# Sheet2.net
KiCad netlist of a schematic drawn in Altium Designer
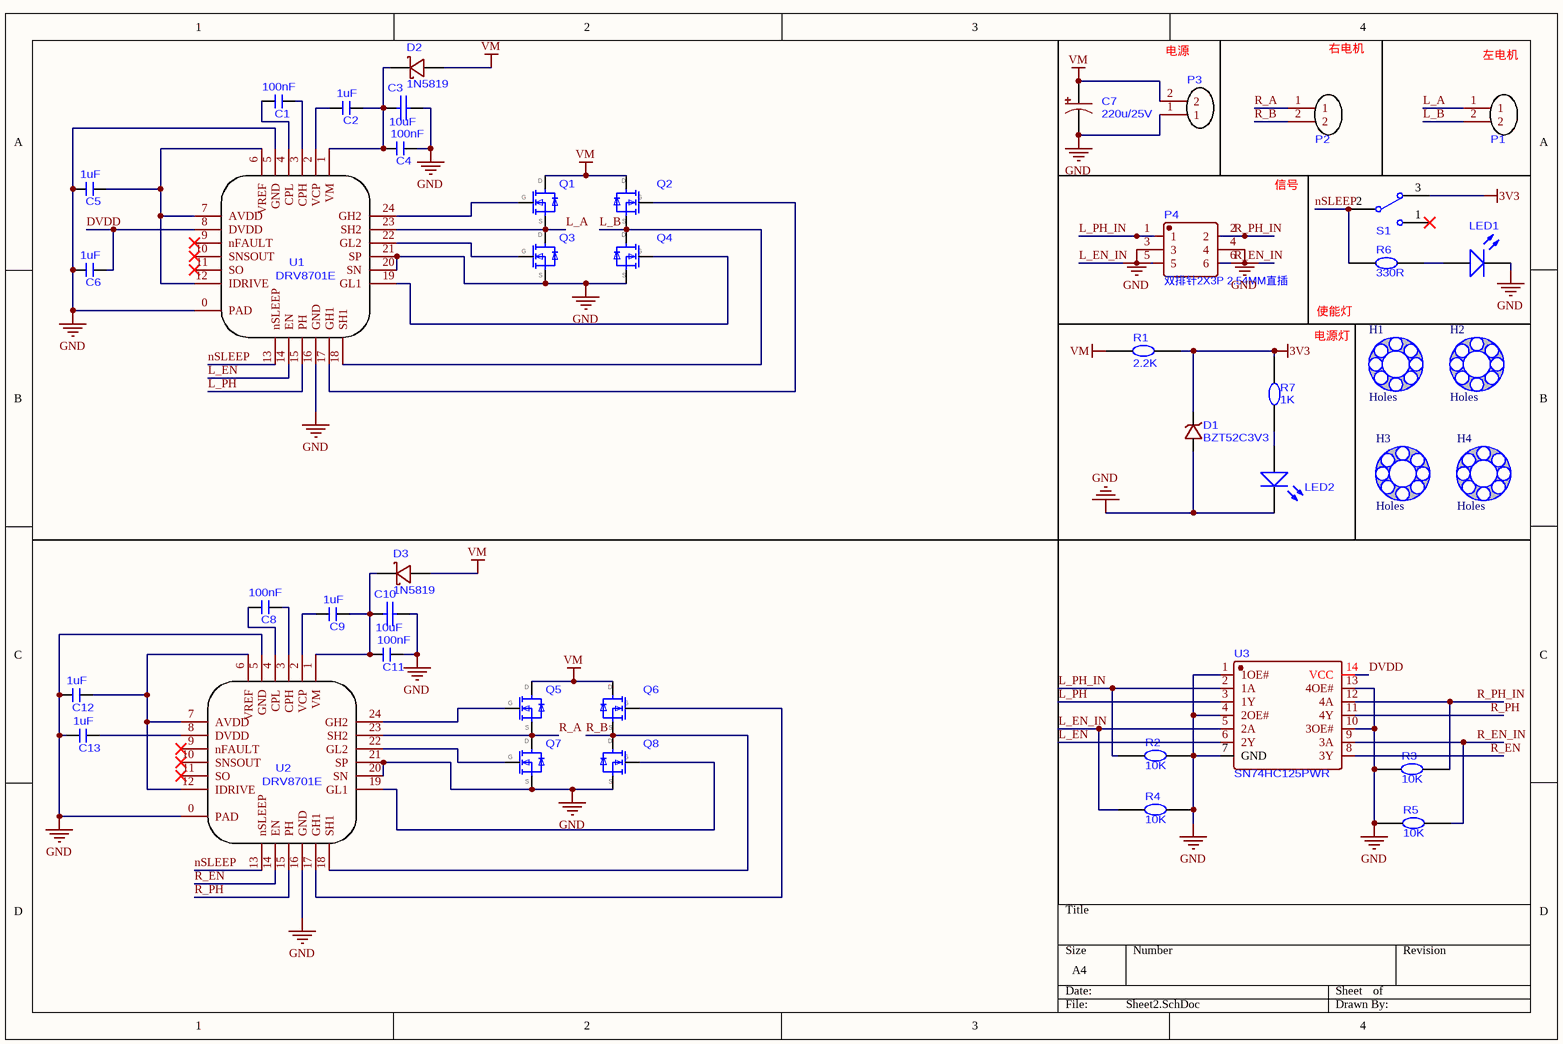
[diagram p0: Sheet2.SchDoc]

(export (version "E")
  (design (tool "Eeschema 10.0.6"))
  (components
    (comp (ref "C1") (value "100nF") (footprint "0603C") (libsource (lib "Schlib1") (part "0603-C")))
    (comp (ref "C2") (value "1uF") (footprint "0603C") (libsource (lib "Schlib1") (part "0603-C")))
    (comp (ref "C3") (value "10uF") (footprint "0805-C") (libsource (lib "Schlib1") (part "0805-C")))
    (comp (ref "C4") (value "100nF") (footprint "0603C") (libsource (lib "Schlib1") (part "0603-C")))
    (comp (ref "C5") (value "1uF") (footprint "0603C") (libsource (lib "Schlib1") (part "0603-C")))
    (comp (ref "C6") (value "1uF") (footprint "0603C") (libsource (lib "Schlib1") (part "0603-C")))
    (comp (ref "C7") (value "220u/25V") (footprint "220UF_25V") (libsource (lib "Schlib1") (part "220u/25V")))
    (comp (ref "C8") (value "100nF") (footprint "0603C") (libsource (lib "Schlib1") (part "0603-C")))
    (comp (ref "C9") (value "1uF") (footprint "0603C") (libsource (lib "Schlib1") (part "0603-C")))
    (comp (ref "C10") (value "10uF") (footprint "0805-C") (libsource (lib "Schlib1") (part "0805-C")))
    (comp (ref "C11") (value "100nF") (footprint "0603C") (libsource (lib "Schlib1") (part "0603-C")))
    (comp (ref "C12") (value "1uF") (footprint "0603C") (libsource (lib "Schlib1") (part "0603-C")))
    (comp (ref "C13") (value "1uF") (footprint "0603C") (libsource (lib "Schlib1") (part "0603-C")))
    (comp (ref "D1") (value "BZT52C3V3") (footprint "SOD-123") (libsource (lib "Schlib1") (part "BZT52C3V3")))
    (comp (ref "D2") (value "1N5819") (footprint "1N5819") (libsource (lib "Schlib1") (part "1N5819")))
    (comp (ref "D3") (value "1N5819") (footprint "1N5819") (libsource (lib "Schlib1") (part "1N5819")))
    (comp (ref "H1")
      (value "Holes")
      (footprint "M3-星月孔")
      (description "holes in the corner of the bord")
      (libsource (lib "Schlib1") (part "星月孔"))
    )
    (comp (ref "H2")
      (value "Holes")
      (footprint "M3-星月孔")
      (description "holes in the corner of the bord")
      (libsource (lib "Schlib1") (part "星月孔"))
    )
    (comp (ref "H3")
      (value "Holes")
      (footprint "M3-星月孔")
      (description "holes in the corner of the bord")
      (libsource (lib "Schlib1") (part "星月孔"))
    )
    (comp (ref "H4")
      (value "Holes")
      (footprint "M3-星月孔")
      (description "holes in the corner of the bord")
      (libsource (lib "Schlib1") (part "星月孔"))
    )
    (comp (ref "LED1") (value "LED") (footprint "0603LED") (libsource (lib "Schlib1") (part "LED")))
    (comp (ref "LED2") (value "LED") (footprint "0603LED") (libsource (lib "Schlib1") (part "LED")))
    (comp (ref "P1") (value "5.08-2P") (footprint "2P-5.08MM") (libsource (lib "Schlib1") (part "5.08-2P")))
    (comp (ref "P2") (value "5.08-2P") (footprint "2P-5.08MM") (libsource (lib "Schlib1") (part "5.08-2P")))
    (comp (ref "P3") (value "5.08-2P") (footprint "2P-5.08MM") (libsource (lib "Schlib1") (part "5.08-2P")))
    (comp (ref "P4")
      (value "双排针2X3P 2.54MM直插")
      (footprint "2X3 2.54")
      (libsource (lib "Schlib1") (part "双排针2X3P 2.54MM直插"))
    )
    (comp (ref "Q1")
      (value "TPH1R403NL_L")
      (footprint "TPH1R403NL")
      (libsource (lib "Schlib1") (part "TPH1R403NL_L"))
    )
    (comp (ref "Q2")
      (value "TPH1R403NL_L")
      (footprint "TPH1R403NL")
      (libsource (lib "") (part "TPH1R403NL_L_1"))
    )
    (comp (ref "Q3")
      (value "TPH1R403NL_L")
      (footprint "TPH1R403NL")
      (libsource (lib "Schlib1") (part "TPH1R403NL_L"))
    )
    (comp (ref "Q4")
      (value "TPH1R403NL_L")
      (footprint "TPH1R403NL")
      (libsource (lib "") (part "TPH1R403NL_L_1"))
    )
    (comp (ref "Q5")
      (value "TPH1R403NL_L")
      (footprint "TPH1R403NL")
      (libsource (lib "Schlib1") (part "TPH1R403NL_L"))
    )
    (comp (ref "Q6")
      (value "TPH1R403NL_L")
      (footprint "TPH1R403NL")
      (libsource (lib "") (part "TPH1R403NL_L_1"))
    )
    (comp (ref "Q7")
      (value "TPH1R403NL_L")
      (footprint "TPH1R403NL")
      (libsource (lib "Schlib1") (part "TPH1R403NL_L"))
    )
    (comp (ref "Q8")
      (value "TPH1R403NL_L")
      (footprint "TPH1R403NL")
      (libsource (lib "") (part "TPH1R403NL_L_1"))
    )
    (comp (ref "R1") (value "2.2K") (footprint "0603R") (libsource (lib "Schlib1") (part "0603-R")))
    (comp (ref "R2") (value "10K") (footprint "0603R") (libsource (lib "Schlib1") (part "0603-R")))
    (comp (ref "R3") (value "10K") (footprint "0603R") (libsource (lib "Schlib1") (part "0603-R")))
    (comp (ref "R4") (value "10K") (footprint "0603R") (libsource (lib "Schlib1") (part "0603-R")))
    (comp (ref "R5") (value "10K") (footprint "0603R") (libsource (lib "Schlib1") (part "0603-R")))
    (comp (ref "R6") (value "330R") (footprint "0603R") (libsource (lib "Schlib1") (part "0603-R")))
    (comp (ref "R7") (value "1K") (footprint "0603R") (libsource (lib "Schlib1") (part "0603-R")))
    (comp (ref "S1")
      (value "SW1:T8013")
      (footprint "SW1_T8013")
      (libsource (lib "Schlib1") (part "SW1{colon}T8013"))
    )
    (comp (ref "U1") (value "DRV8701E") (footprint "DRV8701E") (libsource (lib "Schlib1") (part "DRV8701E")))
    (comp (ref "U2") (value "DRV8701E") (footprint "DRV8701E") (libsource (lib "Schlib1") (part "DRV8701E")))
    (comp (ref "U3")
      (value "SN74HC125PWR")
      (footprint "TSSOP-14_L5.0-W4.4-P0.65-LS6.5-BL")
      (libsource (lib "Schlib1") (part "SN74HC125PWR"))
    )
  )
  (nets
    (net (code "1") (name "/DVDD") (class "Default")
      (node (ref "C6") (pin "2") (pinfunction "2_2") (pintype "passive"))
      (node (ref "U1") (pin "8") (pinfunction "DVDD_8") (pintype "passive"))
      (node (ref "U3") (pin "14") (pinfunction "VCC_14") (pintype "passive"))
    )
    (net (code "2") (name "/L_A") (class "Default")
      (node (ref "P1") (pin "1") (pinfunction "1_1") (pintype "passive"))
      (node (ref "Q1") (pin "3") (pinfunction "S_3") (pintype "passive"))
      (node (ref "Q3") (pin "1") (pinfunction "D_1") (pintype "passive"))
      (node (ref "U1") (pin "23") (pinfunction "SH2_23") (pintype "passive"))
    )
    (net (code "3") (name "/L_B") (class "Default")
      (node (ref "P1") (pin "2") (pinfunction "2_2") (pintype "passive"))
      (node (ref "Q2") (pin "3") (pinfunction "S_3") (pintype "passive"))
      (node (ref "Q4") (pin "1") (pinfunction "D_1") (pintype "passive"))
      (node (ref "U1") (pin "18") (pinfunction "SH1_18") (pintype "passive"))
    )
    (net (code "4") (name "/L_EN") (class "Default")
      (node (ref "U1") (pin "14") (pinfunction "EN_14") (pintype "passive"))
      (node (ref "U3") (pin "6") (pinfunction "2Y_6") (pintype "passive"))
    )
    (net (code "5") (name "/L_EN_IN") (class "Default")
      (node (ref "P4") (pin "5") (pinfunction "5_5") (pintype "passive"))
      (node (ref "R4") (pin "1") (pinfunction "1_1") (pintype "passive"))
      (node (ref "U3") (pin "5") (pinfunction "2A_5") (pintype "passive"))
    )
    (net (code "6") (name "/L_PH") (class "Default")
      (node (ref "U1") (pin "15") (pinfunction "PH_15") (pintype "passive"))
      (node (ref "U3") (pin "3") (pinfunction "1Y_3") (pintype "passive"))
    )
    (net (code "7") (name "/L_PH_IN") (class "Default")
      (node (ref "P4") (pin "1") (pinfunction "1_1") (pintype "passive"))
      (node (ref "R2") (pin "1") (pinfunction "1_1") (pintype "passive"))
      (node (ref "U3") (pin "2") (pinfunction "1A_2") (pintype "passive"))
    )
    (net (code "8") (name "/R_A") (class "Default")
      (node (ref "P2") (pin "1") (pinfunction "1_1") (pintype "passive"))
      (node (ref "Q5") (pin "3") (pinfunction "S_3") (pintype "passive"))
      (node (ref "Q7") (pin "1") (pinfunction "D_1") (pintype "passive"))
      (node (ref "U2") (pin "23") (pinfunction "SH2_23") (pintype "passive"))
    )
    (net (code "9") (name "/R_B") (class "Default")
      (node (ref "P2") (pin "2") (pinfunction "2_2") (pintype "passive"))
      (node (ref "Q6") (pin "3") (pinfunction "S_3") (pintype "passive"))
      (node (ref "Q8") (pin "1") (pinfunction "D_1") (pintype "passive"))
      (node (ref "U2") (pin "18") (pinfunction "SH1_18") (pintype "passive"))
    )
    (net (code "10") (name "/R_EN") (class "Default")
      (node (ref "U2") (pin "14") (pinfunction "EN_14") (pintype "passive"))
      (node (ref "U3") (pin "8") (pinfunction "3Y_8") (pintype "passive"))
    )
    (net (code "11") (name "/R_EN_IN") (class "Default")
      (node (ref "P4") (pin "6") (pinfunction "6_6") (pintype "passive"))
      (node (ref "R5") (pin "2") (pinfunction "2_2") (pintype "passive"))
      (node (ref "U3") (pin "9") (pinfunction "3A_9") (pintype "passive"))
    )
    (net (code "12") (name "/R_PH") (class "Default")
      (node (ref "U2") (pin "15") (pinfunction "PH_15") (pintype "passive"))
      (node (ref "U3") (pin "11") (pinfunction "4Y_11") (pintype "passive"))
    )
    (net (code "13") (name "/R_PH_IN") (class "Default")
      (node (ref "P4") (pin "2") (pinfunction "2_2") (pintype "passive"))
      (node (ref "R3") (pin "2") (pinfunction "2_2") (pintype "passive"))
      (node (ref "U3") (pin "12") (pinfunction "4A_12") (pintype "passive"))
    )
    (net (code "14") (name "/nSLEEP") (class "Default")
      (node (ref "R6") (pin "1") (pinfunction "1_1") (pintype "passive"))
      (node (ref "S1") (pin "2") (pinfunction "2_2") (pintype "passive"))
      (node (ref "U1") (pin "13") (pinfunction "nSLEEP_13") (pintype "passive"))
      (node (ref "U2") (pin "13") (pinfunction "nSLEEP_13") (pintype "passive"))
    )
    (net (code "15") (name "3V3") (class "Default")
      (node (ref "D1") (pin "2") (pinfunction "K_2") (pintype "passive"))
      (node (ref "R1") (pin "2") (pinfunction "2_2") (pintype "passive"))
      (node (ref "R7") (pin "2") (pinfunction "2_2") (pintype "passive"))
      (node (ref "S1") (pin "3") (pinfunction "3_3") (pintype "passive"))
    )
    (net (code "16") (name "GND") (class "Default")
      (node (ref "C10") (pin "1") (pinfunction "1_1") (pintype "passive"))
      (node (ref "C11") (pin "1") (pinfunction "1_1") (pintype "passive"))
      (node (ref "C12") (pin "2") (pinfunction "2_2") (pintype "passive"))
      (node (ref "C13") (pin "1") (pinfunction "1_1") (pintype "passive"))
      (node (ref "C3") (pin "1") (pinfunction "1_1") (pintype "passive"))
      (node (ref "C4") (pin "1") (pinfunction "1_1") (pintype "passive"))
      (node (ref "C5") (pin "2") (pinfunction "2_2") (pintype "passive"))
      (node (ref "C6") (pin "1") (pinfunction "1_1") (pintype "passive"))
      (node (ref "C7") (pin "2") (pinfunction "2_2") (pintype "passive"))
      (node (ref "D1") (pin "1") (pinfunction "A_1") (pintype "passive"))
      (node (ref "LED1") (pin "2") (pinfunction "K_2") (pintype "passive"))
      (node (ref "LED2") (pin "2") (pinfunction "K_2") (pintype "passive"))
      (node (ref "P3") (pin "1") (pinfunction "1_1") (pintype "passive"))
      (node (ref "P4") (pin "3") (pinfunction "3_3") (pintype "passive"))
      (node (ref "P4") (pin "4") (pinfunction "4_4") (pintype "passive"))
      (node (ref "Q3") (pin "3") (pinfunction "S_3") (pintype "passive"))
      (node (ref "Q4") (pin "3") (pinfunction "S_3") (pintype "passive"))
      (node (ref "Q7") (pin "3") (pinfunction "S_3") (pintype "passive"))
      (node (ref "Q8") (pin "3") (pinfunction "S_3") (pintype "passive"))
      (node (ref "R2") (pin "2") (pinfunction "2_2") (pintype "passive"))
      (node (ref "R3") (pin "1") (pinfunction "1_1") (pintype "passive"))
      (node (ref "R4") (pin "2") (pinfunction "2_2") (pintype "passive"))
      (node (ref "R5") (pin "1") (pinfunction "1_1") (pintype "passive"))
      (node (ref "U1") (pin "0") (pinfunction "PAD_0") (pintype "passive"))
      (node (ref "U1") (pin "16") (pinfunction "GND_16") (pintype "passive"))
      (node (ref "U1") (pin "20") (pinfunction "SN_20") (pintype "passive"))
      (node (ref "U1") (pin "21") (pinfunction "SP_21") (pintype "passive"))
      (node (ref "U1") (pin "5") (pinfunction "GND_5") (pintype "passive"))
      (node (ref "U2") (pin "0") (pinfunction "PAD_0") (pintype "passive"))
      (node (ref "U2") (pin "16") (pinfunction "GND_16") (pintype "passive"))
      (node (ref "U2") (pin "20") (pinfunction "SN_20") (pintype "passive"))
      (node (ref "U2") (pin "21") (pinfunction "SP_21") (pintype "passive"))
      (node (ref "U2") (pin "5") (pinfunction "GND_5") (pintype "passive"))
      (node (ref "U3") (pin "1") (pinfunction "1OE#_1") (pintype "passive"))
      (node (ref "U3") (pin "10") (pinfunction "3OE#_10") (pintype "passive"))
      (node (ref "U3") (pin "13") (pinfunction "4OE#_13") (pintype "passive"))
      (node (ref "U3") (pin "4") (pinfunction "2OE#_4") (pintype "passive"))
      (node (ref "U3") (pin "7") (pinfunction "GND_7") (pintype "passive"))
    )
    (net (code "17") (name "Net-(LED1-Pad1)") (class "Default")
      (node (ref "LED1") (pin "1") (pinfunction "1_1") (pintype "passive"))
      (node (ref "R6") (pin "2") (pinfunction "2_2") (pintype "passive"))
    )
    (net (code "18") (name "Net-(LED2-Pad1)") (class "Default")
      (node (ref "LED2") (pin "1") (pinfunction "1_1") (pintype "passive"))
      (node (ref "R7") (pin "1") (pinfunction "1_1") (pintype "passive"))
    )
    (net (code "19") (name "Net-(Q1-G)") (class "Default")
      (node (ref "Q1") (pin "2") (pinfunction "G_2") (pintype "passive"))
      (node (ref "U1") (pin "24") (pinfunction "GH2_24") (pintype "passive"))
    )
    (net (code "20") (name "Net-(Q2-G)") (class "Default")
      (node (ref "Q2") (pin "2") (pinfunction "G_2") (pintype "passive"))
      (node (ref "U1") (pin "17") (pinfunction "GH1_17") (pintype "passive"))
    )
    (net (code "21") (name "Net-(Q3-G)") (class "Default")
      (node (ref "Q3") (pin "2") (pinfunction "G_2") (pintype "passive"))
      (node (ref "U1") (pin "22") (pinfunction "GL2_22") (pintype "passive"))
    )
    (net (code "22") (name "Net-(Q4-G)") (class "Default")
      (node (ref "Q4") (pin "2") (pinfunction "G_2") (pintype "passive"))
      (node (ref "U1") (pin "19") (pinfunction "GL1_19") (pintype "passive"))
    )
    (net (code "23") (name "Net-(Q5-G)") (class "Default")
      (node (ref "Q5") (pin "2") (pinfunction "G_2") (pintype "passive"))
      (node (ref "U2") (pin "24") (pinfunction "GH2_24") (pintype "passive"))
    )
    (net (code "24") (name "Net-(Q6-G)") (class "Default")
      (node (ref "Q6") (pin "2") (pinfunction "G_2") (pintype "passive"))
      (node (ref "U2") (pin "17") (pinfunction "GH1_17") (pintype "passive"))
    )
    (net (code "25") (name "Net-(Q7-G)") (class "Default")
      (node (ref "Q7") (pin "2") (pinfunction "G_2") (pintype "passive"))
      (node (ref "U2") (pin "22") (pinfunction "GL2_22") (pintype "passive"))
    )
    (net (code "26") (name "Net-(Q8-G)") (class "Default")
      (node (ref "Q8") (pin "2") (pinfunction "G_2") (pintype "passive"))
      (node (ref "U2") (pin "19") (pinfunction "GL1_19") (pintype "passive"))
    )
    (net (code "27") (name "Net-(U1-AVDD)") (class "Default")
      (node (ref "C5") (pin "1") (pinfunction "1_1") (pintype "passive"))
      (node (ref "U1") (pin "12") (pinfunction "IDRIVE_12") (pintype "passive"))
      (node (ref "U1") (pin "6") (pinfunction "VREF_6") (pintype "passive"))
      (node (ref "U1") (pin "7") (pinfunction "AVDD_7") (pintype "passive"))
    )
    (net (code "28") (name "Net-(U1-CPH)") (class "Default")
      (node (ref "C1") (pin "2") (pinfunction "2_2") (pintype "passive"))
      (node (ref "U1") (pin "3") (pinfunction "CPH_3") (pintype "passive"))
    )
    (net (code "29") (name "Net-(U1-CPL)") (class "Default")
      (node (ref "C1") (pin "1") (pinfunction "1_1") (pintype "passive"))
      (node (ref "U1") (pin "4") (pinfunction "CPL_4") (pintype "passive"))
    )
    (net (code "30") (name "Net-(U1-VCP)") (class "Default")
      (node (ref "C2") (pin "2") (pinfunction "2_2") (pintype "passive"))
      (node (ref "U1") (pin "2") (pinfunction "VCP_2") (pintype "passive"))
    )
    (net (code "31") (name "Net-(U1-VM)") (class "Default")
      (node (ref "C2") (pin "1") (pinfunction "1_1") (pintype "passive"))
      (node (ref "C3") (pin "2") (pinfunction "2_2") (pintype "passive"))
      (node (ref "C4") (pin "2") (pinfunction "2_2") (pintype "passive"))
      (node (ref "D2") (pin "1") (pinfunction "1_1") (pintype "passive"))
      (node (ref "U1") (pin "1") (pinfunction "VM_1") (pintype "passive"))
    )
    (net (code "32") (name "Net-(U2-AVDD)") (class "Default")
      (node (ref "C12") (pin "1") (pinfunction "1_1") (pintype "passive"))
      (node (ref "U2") (pin "12") (pinfunction "IDRIVE_12") (pintype "passive"))
      (node (ref "U2") (pin "6") (pinfunction "VREF_6") (pintype "passive"))
      (node (ref "U2") (pin "7") (pinfunction "AVDD_7") (pintype "passive"))
    )
    (net (code "33") (name "Net-(U2-CPH)") (class "Default")
      (node (ref "C8") (pin "2") (pinfunction "2_2") (pintype "passive"))
      (node (ref "U2") (pin "3") (pinfunction "CPH_3") (pintype "passive"))
    )
    (net (code "34") (name "Net-(U2-CPL)") (class "Default")
      (node (ref "C8") (pin "1") (pinfunction "1_1") (pintype "passive"))
      (node (ref "U2") (pin "4") (pinfunction "CPL_4") (pintype "passive"))
    )
    (net (code "35") (name "Net-(U2-DVDD)") (class "Default")
      (node (ref "C13") (pin "2") (pinfunction "2_2") (pintype "passive"))
      (node (ref "U2") (pin "8") (pinfunction "DVDD_8") (pintype "passive"))
    )
    (net (code "36") (name "Net-(U2-VCP)") (class "Default")
      (node (ref "C9") (pin "2") (pinfunction "2_2") (pintype "passive"))
      (node (ref "U2") (pin "2") (pinfunction "VCP_2") (pintype "passive"))
    )
    (net (code "37") (name "Net-(U2-VM)") (class "Default")
      (node (ref "C10") (pin "2") (pinfunction "2_2") (pintype "passive"))
      (node (ref "C11") (pin "2") (pinfunction "2_2") (pintype "passive"))
      (node (ref "C9") (pin "1") (pinfunction "1_1") (pintype "passive"))
      (node (ref "D3") (pin "1") (pinfunction "1_1") (pintype "passive"))
      (node (ref "U2") (pin "1") (pinfunction "VM_1") (pintype "passive"))
    )
    (net (code "38") (name "VM") (class "Default")
      (node (ref "C7") (pin "1") (pinfunction "1_1") (pintype "passive"))
      (node (ref "D2") (pin "2") (pinfunction "2_2") (pintype "passive"))
      (node (ref "D3") (pin "2") (pinfunction "2_2") (pintype "passive"))
      (node (ref "P3") (pin "2") (pinfunction "2_2") (pintype "passive"))
      (node (ref "Q1") (pin "1") (pinfunction "D_1") (pintype "passive"))
      (node (ref "Q2") (pin "1") (pinfunction "D_1") (pintype "passive"))
      (node (ref "Q5") (pin "1") (pinfunction "D_1") (pintype "passive"))
      (node (ref "Q6") (pin "1") (pinfunction "D_1") (pintype "passive"))
      (node (ref "R1") (pin "1") (pinfunction "1_1") (pintype "passive"))
    )
    (net (code "39") (name "unconnected-(S1-Pad1)") (class "Default")
      (node (ref "S1") (pin "1") (pinfunction "1_1") (pintype "passive+no_connect"))
    )
    (net (code "40") (name "unconnected-(U1-SNSOUT-Pad10)") (class "Default")
      (node (ref "U1") (pin "10") (pinfunction "SNSOUT_10") (pintype "passive+no_connect"))
    )
    (net (code "41") (name "unconnected-(U1-SO-Pad11)") (class "Default")
      (node (ref "U1") (pin "11") (pinfunction "SO_11") (pintype "passive+no_connect"))
    )
    (net (code "42") (name "unconnected-(U1-nFAULT-Pad9)") (class "Default")
      (node (ref "U1") (pin "9") (pinfunction "nFAULT_9") (pintype "passive+no_connect"))
    )
    (net (code "43") (name "unconnected-(U2-SNSOUT-Pad10)") (class "Default")
      (node (ref "U2") (pin "10") (pinfunction "SNSOUT_10") (pintype "passive+no_connect"))
    )
    (net (code "44") (name "unconnected-(U2-SO-Pad11)") (class "Default")
      (node (ref "U2") (pin "11") (pinfunction "SO_11") (pintype "passive+no_connect"))
    )
    (net (code "45") (name "unconnected-(U2-nFAULT-Pad9)") (class "Default")
      (node (ref "U2") (pin "9") (pinfunction "nFAULT_9") (pintype "passive+no_connect"))
    )
  )
)
